# Buck_100V.net
KiCad netlist of a schematic drawn in EAGLE
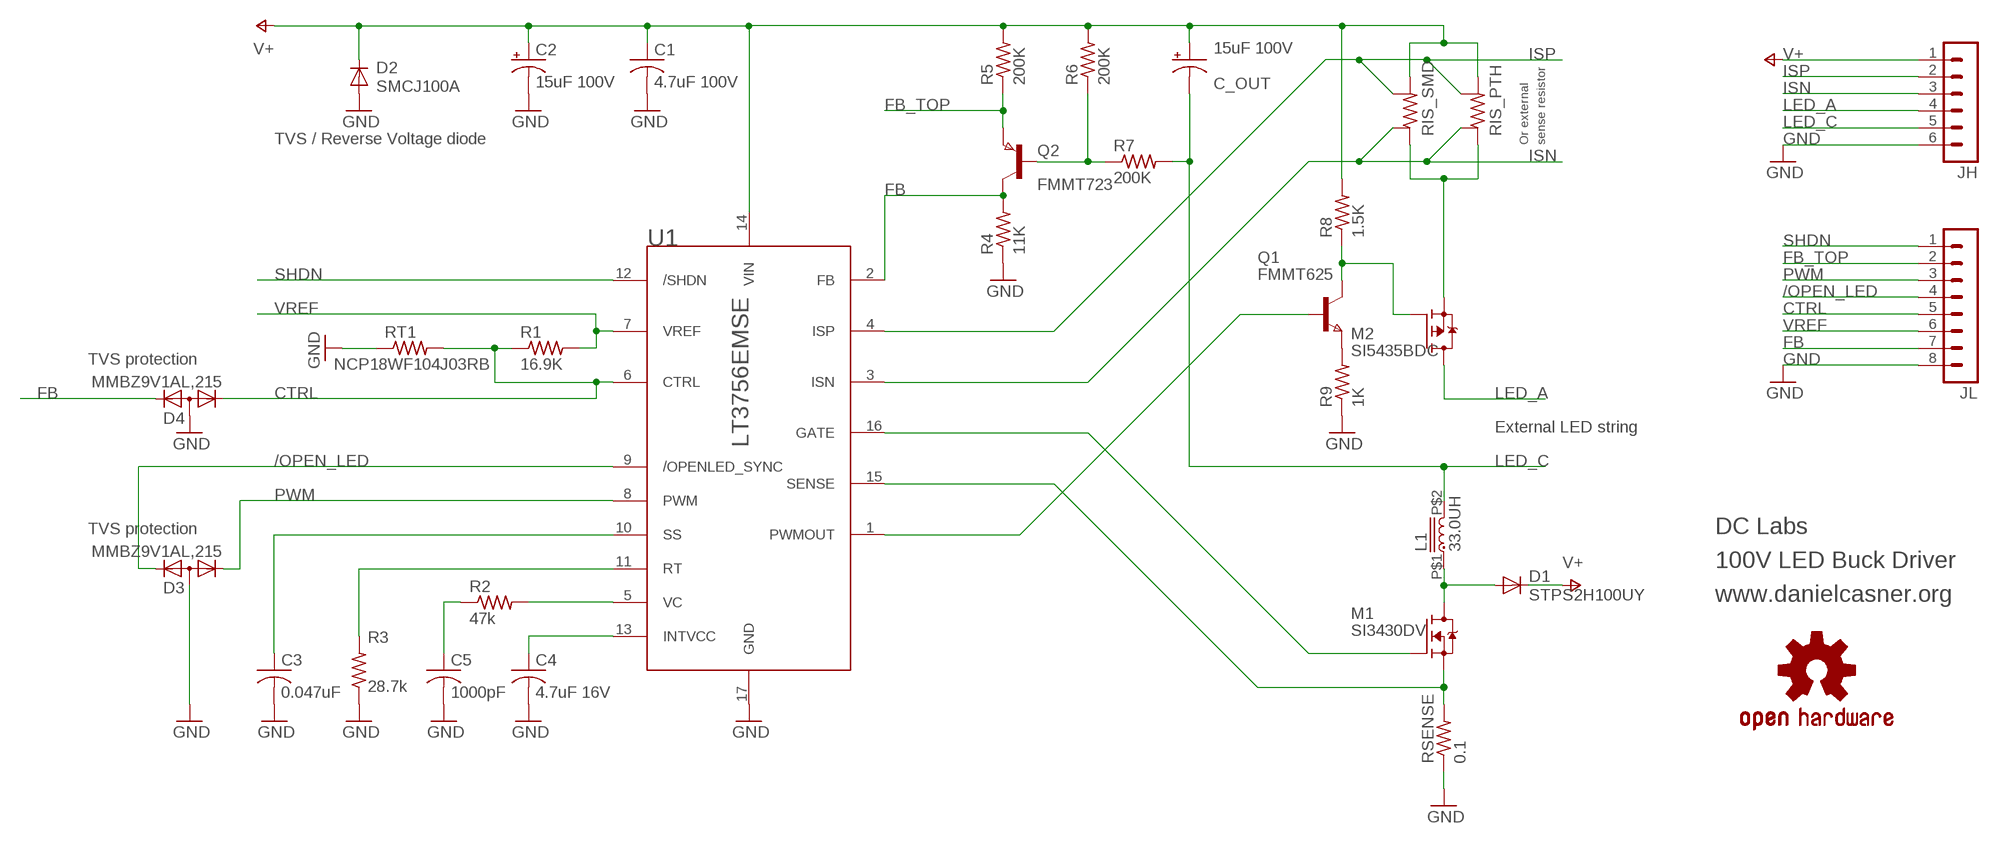
[diagram p0: schematic, sheet 1]

(export (version "E")
  (design (tool "Eeschema 10.0.6"))
  (components
    (comp (ref "C1")
      (value "4.7uF 100V")
      (footprint "eagle-import:C2220K")
      (libsource (lib "eagle-import") (part "C-USC2220K"))
    )
    (comp (ref "C2")
      (value "15uF 100V")
      (footprint "eagle-import:E2,5-6E")
      (libsource (lib "eagle-import") (part "CPOL-USE2,5-6E"))
    )
    (comp (ref "C3")
      (value "0.047uF")
      (footprint "eagle-import:C0805")
      (libsource (lib "eagle-import") (part "C-USC0805"))
    )
    (comp (ref "C4")
      (value "4.7uF 16V")
      (footprint "eagle-import:C0805")
      (libsource (lib "eagle-import") (part "C-USC0805"))
    )
    (comp (ref "C5")
      (value "1000pF")
      (footprint "eagle-import:C0805")
      (libsource (lib "eagle-import") (part "C-USC0805"))
    )
    (comp (ref "C_OUT")
      (value "15uF 100V")
      (footprint "eagle-import:E2,5-6E")
      (libsource (lib "eagle-import") (part "CPOL-USE2,5-6E"))
    )
    (comp (ref "D1")
      (value "STPS2H100UY")
      (footprint "eagle-import:SMB")
      (libsource (lib "eagle-import") (part "DIODE-SMB"))
    )
    (comp (ref "D2")
      (value "SMCJ100A")
      (footprint "eagle-import:SMC")
      (libsource (lib "eagle-import") (part "DIODE-SMC"))
    )
    (comp (ref "D3")
      (value "MMBZ9V1AL,215")
      (footprint "eagle-import:SOT23")
      (libsource (lib "eagle-import") (part "DIODE-2CA|ACSOT23"))
    )
    (comp (ref "D4")
      (value "MMBZ9V1AL,215")
      (footprint "eagle-import:SOT23")
      (libsource (lib "eagle-import") (part "DIODE-2CA|ACSOT23"))
    )
    (comp (ref "JH")
      (value "MA06-1")
      (footprint "eagle-import:MA06-1")
      (libsource (lib "eagle-import") (part "MA06-1"))
    )
    (comp (ref "JL")
      (value "MA08-1")
      (footprint "eagle-import:MA08-1")
      (libsource (lib "eagle-import") (part "MA08-1"))
    )
    (comp (ref "L1")
      (value "33.0UH")
      (footprint "eagle-import:ASPI-0612FS")
      (libsource (lib "eagle-import") (part "ASPI-0612FS"))
    )
    (comp (ref "M1")
      (value "SI3430DV")
      (footprint "eagle-import:SSOT6")
      (libsource (lib "eagle-import") (part "SI3430DV"))
    )
    (comp (ref "M2")
      (value "SI5435BDC")
      (footprint "eagle-import:1206-8CHIP-FET")
      (libsource (lib "eagle-import") (part "SI5435BDC"))
    )
    (comp (ref "Q1")
      (value "FMMT625")
      (footprint "eagle-import:SOT-23")
      (fields (field (name "MPN") "FMMT618"))
      (libsource (lib "eagle-import") (part "FMMT625"))
    )
    (comp (ref "Q2")
      (value "FMMT723")
      (footprint "eagle-import:SOT-23")
      (libsource (lib "eagle-import") (part "FMMT723"))
    )
    (comp (ref "R1")
      (value "16.9K")
      (footprint "eagle-import:R0805")
      (libsource (lib "eagle-import") (part "R-US_R0805"))
    )
    (comp (ref "R2")
      (value "47k")
      (footprint "eagle-import:R0805")
      (libsource (lib "eagle-import") (part "R-US_R0805"))
    )
    (comp (ref "R3")
      (value "28.7k")
      (footprint "eagle-import:R0805")
      (libsource (lib "eagle-import") (part "R-US_R0805"))
    )
    (comp (ref "R4")
      (value "11K")
      (footprint "eagle-import:R0805")
      (libsource (lib "eagle-import") (part "R-US_R0805"))
    )
    (comp (ref "R5")
      (value "200K")
      (footprint "eagle-import:R0805")
      (libsource (lib "eagle-import") (part "R-US_R0805"))
    )
    (comp (ref "R6")
      (value "200K")
      (footprint "eagle-import:R0805")
      (libsource (lib "eagle-import") (part "R-US_R0805"))
    )
    (comp (ref "R7")
      (value "200K")
      (footprint "eagle-import:R0805")
      (libsource (lib "eagle-import") (part "R-US_R0805"))
    )
    (comp (ref "R8")
      (value "1.5K")
      (footprint "eagle-import:R0805")
      (libsource (lib "eagle-import") (part "R-US_R0805"))
    )
    (comp (ref "R9")
      (value "1K")
      (footprint "eagle-import:R0805")
      (libsource (lib "eagle-import") (part "R-US_R0805"))
    )
    (comp (ref "RIS_PTH")
      (value "R-KELVIN0204/7")
      (footprint "eagle-import:0204_7-KELVIN")
      (libsource (lib "eagle-import") (part "R-KELVIN0204/7"))
    )
    (comp (ref "RIS_SMD")
      (value "R-KELVINR2512")
      (footprint "eagle-import:R2512_KELVIN")
      (libsource (lib "eagle-import") (part "R-KELVINR2512"))
    )
    (comp (ref "RSENSE")
      (value "0.1")
      (footprint "eagle-import:R0805")
      (libsource (lib "eagle-import") (part "R-US_R0805"))
    )
    (comp (ref "RT1")
      (value "NCP18WF104J03RB")
      (footprint "eagle-import:R0805")
      (libsource (lib "eagle-import") (part "R-US_R0805"))
    )
    (comp (ref "U$1")
      (value "OSHW-LOGOS")
      (footprint "eagle-import:OSHW-LOGO-S")
      (libsource (lib "eagle-import") (part "OSHW-LOGOS"))
    )
    (comp (ref "U1")
      (value "LT3756EMSE")
      (footprint "eagle-import:MSOP16EXP")
      (libsource (lib "eagle-import") (part "LT3756EMSE"))
    )
  )
  (nets
    (net (code "1") (name "/CTRL") (class "Default")
      (node (ref "D4") (pin "1") (pinfunction "K1_1") (pintype "passive"))
      (node (ref "JL") (pin "5") (pinfunction "5_5") (pintype "passive"))
      (node (ref "R1") (pin "1") (pinfunction "1_1") (pintype "passive"))
      (node (ref "RT1") (pin "2") (pinfunction "2_2") (pintype "passive"))
      (node (ref "U1") (pin "6") (pinfunction "CTRL_6") (pintype "bidirectional"))
    )
    (net (code "2") (name "/FB") (class "Default")
      (node (ref "D4") (pin "2") (pinfunction "K2_2") (pintype "passive"))
      (node (ref "JL") (pin "7") (pinfunction "7_7") (pintype "passive"))
      (node (ref "Q2") (pin "1") (pinfunction "C_1") (pintype "passive"))
      (node (ref "R4") (pin "2") (pinfunction "2_2") (pintype "passive"))
      (node (ref "U1") (pin "2") (pinfunction "FB_2") (pintype "bidirectional"))
    )
    (net (code "3") (name "/FB_TOP") (class "Default")
      (node (ref "JL") (pin "2") (pinfunction "2_2") (pintype "passive"))
      (node (ref "Q2") (pin "2") (pinfunction "E_2") (pintype "passive"))
      (node (ref "R5") (pin "1") (pinfunction "1_1") (pintype "passive"))
    )
    (net (code "4") (name "/ISN") (class "Default")
      (node (ref "JH") (pin "3") (pinfunction "3_3") (pintype "passive"))
      (node (ref "RIS_PTH") (pin "1S") (pinfunction "P$1_1S") (pintype "output"))
      (node (ref "RIS_SMD") (pin "1S") (pinfunction "P$1_1S") (pintype "output"))
      (node (ref "U1") (pin "3") (pinfunction "ISN_3") (pintype "bidirectional"))
    )
    (net (code "5") (name "/ISP") (class "Default")
      (node (ref "JH") (pin "2") (pinfunction "2_2") (pintype "passive"))
      (node (ref "RIS_PTH") (pin "2S") (pinfunction "P$2_2S") (pintype "output"))
      (node (ref "RIS_SMD") (pin "2S") (pinfunction "P$2_2S") (pintype "output"))
      (node (ref "U1") (pin "4") (pinfunction "ISP_4") (pintype "bidirectional"))
    )
    (net (code "6") (name "/LED_A") (class "Default")
      (node (ref "JH") (pin "4") (pinfunction "4_4") (pintype "passive"))
      (node (ref "M2") (pin "1") (pinfunction "D_1") (pintype "passive"))
      (node (ref "M2") (pin "2") (pinfunction "D_2") (pintype "passive"))
      (node (ref "M2") (pin "3") (pinfunction "D_3") (pintype "passive"))
      (node (ref "M2") (pin "6") (pinfunction "D_6") (pintype "passive"))
      (node (ref "M2") (pin "7") (pinfunction "D_7") (pintype "passive"))
      (node (ref "M2") (pin "8") (pinfunction "D_8") (pintype "passive"))
    )
    (net (code "7") (name "/LED_C") (class "Default")
      (node (ref "C_OUT") (pin "-") (pinfunction "-_-") (pintype "passive"))
      (node (ref "JH") (pin "5") (pinfunction "5_5") (pintype "passive"))
      (node (ref "L1") (pin "P$2") (pinfunction "2_P$2") (pintype "passive"))
      (node (ref "R7") (pin "2") (pinfunction "2_2") (pintype "passive"))
    )
    (net (code "8") (name "/PWM") (class "Default")
      (node (ref "D3") (pin "1") (pinfunction "K1_1") (pintype "passive"))
      (node (ref "JL") (pin "3") (pinfunction "3_3") (pintype "passive"))
      (node (ref "U1") (pin "8") (pinfunction "PWM_8") (pintype "bidirectional"))
    )
    (net (code "9") (name "/SHDN") (class "Default")
      (node (ref "JL") (pin "1") (pinfunction "1_1") (pintype "passive"))
      (node (ref "U1") (pin "12") (pinfunction "/SHDN_12") (pintype "bidirectional"))
    )
    (net (code "10") (name "/VREF") (class "Default")
      (node (ref "JL") (pin "6") (pinfunction "6_6") (pintype "passive"))
      (node (ref "R1") (pin "2") (pinfunction "2_2") (pintype "passive"))
      (node (ref "U1") (pin "7") (pinfunction "VREF_7") (pintype "output"))
    )
    (net (code "11") (name "/{slash}OPEN_LED") (class "Default")
      (node (ref "D3") (pin "2") (pinfunction "K2_2") (pintype "passive"))
      (node (ref "JL") (pin "4") (pinfunction "4_4") (pintype "passive"))
      (node (ref "U1") (pin "9") (pinfunction "/OPENLED_SYNC_9") (pintype "output"))
    )
    (net (code "12") (name "GND") (class "Default")
      (node (ref "C1") (pin "2") (pinfunction "2_2") (pintype "passive"))
      (node (ref "C2") (pin "-") (pinfunction "-_-") (pintype "passive"))
      (node (ref "C3") (pin "2") (pinfunction "2_2") (pintype "passive"))
      (node (ref "C4") (pin "2") (pinfunction "2_2") (pintype "passive"))
      (node (ref "C5") (pin "2") (pinfunction "2_2") (pintype "passive"))
      (node (ref "D2") (pin "A") (pinfunction "A_A") (pintype "passive"))
      (node (ref "D3") (pin "3") (pinfunction "A_3") (pintype "passive"))
      (node (ref "D4") (pin "3") (pinfunction "A_3") (pintype "passive"))
      (node (ref "JH") (pin "6") (pinfunction "6_6") (pintype "passive"))
      (node (ref "JL") (pin "8") (pinfunction "8_8") (pintype "passive"))
      (node (ref "R3") (pin "1") (pinfunction "1_1") (pintype "passive"))
      (node (ref "R4") (pin "1") (pinfunction "1_1") (pintype "passive"))
      (node (ref "R9") (pin "1") (pinfunction "1_1") (pintype "passive"))
      (node (ref "RSENSE") (pin "1") (pinfunction "1_1") (pintype "passive"))
      (node (ref "RT1") (pin "1") (pinfunction "1_1") (pintype "passive"))
      (node (ref "U1") (pin "17") (pinfunction "GND_17") (pintype "power_in"))
    )
    (net (code "13") (name "Net-(C5-Pad1)") (class "Default")
      (node (ref "C5") (pin "1") (pinfunction "1_1") (pintype "passive"))
      (node (ref "R2") (pin "1") (pinfunction "1_1") (pintype "passive"))
    )
    (net (code "14") (name "Net-(L1-1)") (class "Default")
      (node (ref "D1") (pin "A") (pinfunction "A_A") (pintype "passive"))
      (node (ref "L1") (pin "P$1") (pinfunction "1_P$1") (pintype "passive"))
      (node (ref "M1") (pin "1") (pinfunction "D_1") (pintype "passive"))
      (node (ref "M1") (pin "2") (pinfunction "D_2") (pintype "passive"))
      (node (ref "M1") (pin "5") (pinfunction "D_5") (pintype "passive"))
      (node (ref "M1") (pin "6") (pinfunction "D_6") (pintype "passive"))
    )
    (net (code "15") (name "Net-(M1-G)") (class "Default")
      (node (ref "M1") (pin "3") (pinfunction "G_3") (pintype "passive"))
      (node (ref "U1") (pin "16") (pinfunction "GATE_16") (pintype "bidirectional"))
    )
    (net (code "16") (name "Net-(M1-S)") (class "Default")
      (node (ref "M1") (pin "4") (pinfunction "S_4") (pintype "passive"))
      (node (ref "RSENSE") (pin "2") (pinfunction "2_2") (pintype "passive"))
      (node (ref "U1") (pin "15") (pinfunction "SENSE_15") (pintype "bidirectional"))
    )
    (net (code "17") (name "Net-(M2-G)") (class "Default")
      (node (ref "M2") (pin "4") (pinfunction "G_4") (pintype "passive"))
      (node (ref "Q1") (pin "1") (pinfunction "C_1") (pintype "passive"))
      (node (ref "R8") (pin "1") (pinfunction "1_1") (pintype "passive"))
    )
    (net (code "18") (name "Net-(M2-S)") (class "Default")
      (node (ref "M2") (pin "5") (pinfunction "S_5") (pintype "passive"))
      (node (ref "RIS_PTH") (pin "1") (pinfunction "1_1") (pintype "passive"))
      (node (ref "RIS_SMD") (pin "1") (pinfunction "1_1") (pintype "passive"))
    )
    (net (code "19") (name "Net-(Q1-B)") (class "Default")
      (node (ref "Q1") (pin "3") (pinfunction "B_3") (pintype "passive"))
      (node (ref "U1") (pin "1") (pinfunction "PWMOUT_1") (pintype "bidirectional"))
    )
    (net (code "20") (name "Net-(Q1-E)") (class "Default")
      (node (ref "Q1") (pin "2") (pinfunction "E_2") (pintype "passive"))
      (node (ref "R9") (pin "2") (pinfunction "2_2") (pintype "passive"))
    )
    (net (code "21") (name "Net-(Q2-B)") (class "Default")
      (node (ref "Q2") (pin "3") (pinfunction "B_3") (pintype "passive"))
      (node (ref "R6") (pin "1") (pinfunction "1_1") (pintype "passive"))
      (node (ref "R7") (pin "1") (pinfunction "1_1") (pintype "passive"))
    )
    (net (code "22") (name "Net-(U1-INTVCC)") (class "Default")
      (node (ref "C4") (pin "1") (pinfunction "1_1") (pintype "passive"))
      (node (ref "U1") (pin "13") (pinfunction "INTVCC_13") (pintype "power_in"))
    )
    (net (code "23") (name "Net-(U1-RT)") (class "Default")
      (node (ref "R3") (pin "2") (pinfunction "2_2") (pintype "passive"))
      (node (ref "U1") (pin "11") (pinfunction "RT_11") (pintype "bidirectional"))
    )
    (net (code "24") (name "Net-(U1-SS)") (class "Default")
      (node (ref "C3") (pin "1") (pinfunction "1_1") (pintype "passive"))
      (node (ref "U1") (pin "10") (pinfunction "SS_10") (pintype "bidirectional"))
    )
    (net (code "25") (name "Net-(U1-VC)") (class "Default")
      (node (ref "R2") (pin "2") (pinfunction "2_2") (pintype "passive"))
      (node (ref "U1") (pin "5") (pinfunction "VC_5") (pintype "bidirectional"))
    )
    (net (code "26") (name "V+") (class "Default")
      (node (ref "C1") (pin "1") (pinfunction "1_1") (pintype "passive"))
      (node (ref "C2") (pin "+") (pinfunction "+_+") (pintype "passive"))
      (node (ref "C_OUT") (pin "+") (pinfunction "+_+") (pintype "passive"))
      (node (ref "D1") (pin "C") (pinfunction "C_C") (pintype "passive"))
      (node (ref "D2") (pin "C") (pinfunction "C_C") (pintype "passive"))
      (node (ref "JH") (pin "1") (pinfunction "1_1") (pintype "passive"))
      (node (ref "R5") (pin "2") (pinfunction "2_2") (pintype "passive"))
      (node (ref "R6") (pin "2") (pinfunction "2_2") (pintype "passive"))
      (node (ref "R8") (pin "2") (pinfunction "2_2") (pintype "passive"))
      (node (ref "RIS_PTH") (pin "2") (pinfunction "2_2") (pintype "passive"))
      (node (ref "RIS_SMD") (pin "2") (pinfunction "2_2") (pintype "passive"))
      (node (ref "U1") (pin "14") (pinfunction "VIN_14") (pintype "power_in"))
    )
  )
)
